# Steering_IOSch.net
KiCad netlist of a schematic drawn in Altium Designer
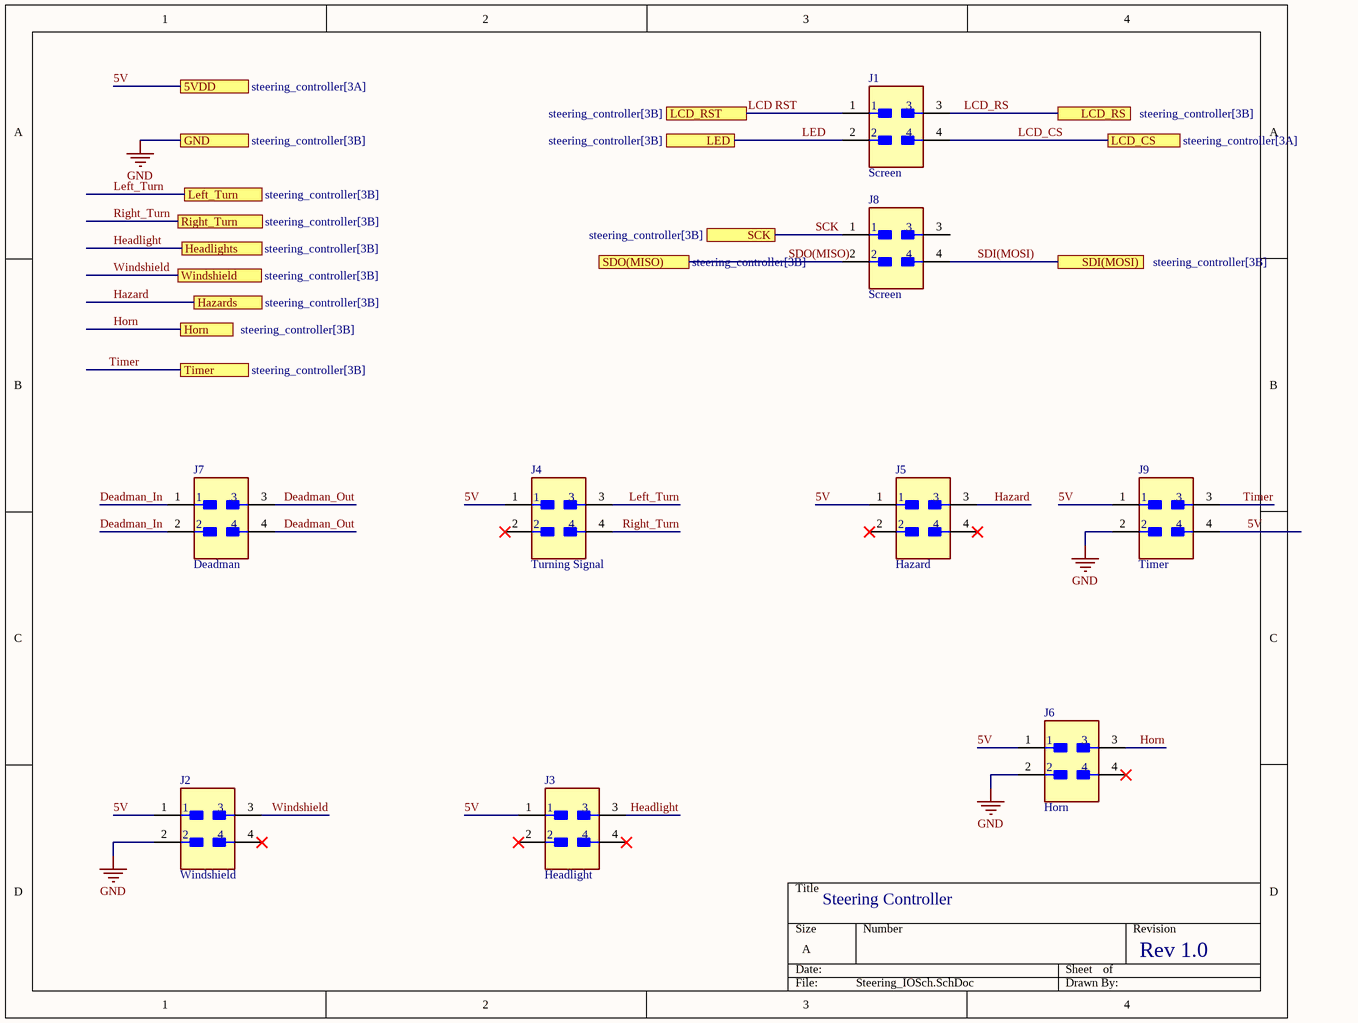
[diagram p0: Steering_IOSch.SchDoc]

(export (version "E")
  (design (tool "Eeschema 10.0.6"))
  (components
    (comp (ref "J1")
      (value "Screen")
      (footprint "asib:FP-0039281043-MFG")
      (description "CONN HEADER VERT 4POS 4.2MM. 0039281043")
      (fields (field (name "MANUFACTURER PART NUMBER") "0039281043") (field (name "MANUFACTURER") "Molex"))
      (libsource (lib "asib") (part "1x4_FEMALE_POWER"))
    )
    (comp (ref "J2")
      (value "Windshield")
      (footprint "asib:FP-0039281043-MFG")
      (description "CONN HEADER VERT 4POS 4.2MM. 0039281043")
      (fields (field (name "MANUFACTURER PART NUMBER") "0039281043") (field (name "MANUFACTURER") "Molex"))
      (libsource (lib "asib") (part "1x4_FEMALE_POWER"))
    )
    (comp (ref "J3")
      (value "Headlight")
      (footprint "asib:FP-0039281043-MFG")
      (description "CONN HEADER VERT 4POS 4.2MM. 0039281043")
      (fields (field (name "MANUFACTURER PART NUMBER") "0039281043") (field (name "MANUFACTURER") "Molex"))
      (libsource (lib "asib") (part "1x4_FEMALE_POWER"))
    )
    (comp (ref "J4")
      (value "Turning Signal")
      (footprint "asib:FP-0039281043-MFG")
      (description "CONN HEADER VERT 4POS 4.2MM. 0039281043")
      (fields (field (name "MANUFACTURER PART NUMBER") "0039281043") (field (name "MANUFACTURER") "Molex"))
      (libsource (lib "asib") (part "1x4_FEMALE_POWER"))
    )
    (comp (ref "J5")
      (value "Hazard")
      (footprint "asib:FP-0039281043-MFG")
      (description "CONN HEADER VERT 4POS 4.2MM. 0039281043")
      (fields (field (name "MANUFACTURER PART NUMBER") "0039281043") (field (name "MANUFACTURER") "Molex"))
      (libsource (lib "asib") (part "1x4_FEMALE_POWER"))
    )
    (comp (ref "J6")
      (value "Horn")
      (footprint "asib:FP-0039281043-MFG")
      (description "CONN HEADER VERT 4POS 4.2MM. 0039281043")
      (fields (field (name "MANUFACTURER PART NUMBER") "0039281043") (field (name "MANUFACTURER") "Molex"))
      (libsource (lib "asib") (part "1x4_FEMALE_POWER"))
    )
    (comp (ref "J7")
      (value "Deadman")
      (footprint "asib:FP-0039281043-MFG")
      (description "CONN HEADER VERT 4POS 4.2MM. 0039281043")
      (fields (field (name "MANUFACTURER PART NUMBER") "0039281043") (field (name "MANUFACTURER") "Molex"))
      (libsource (lib "asib") (part "1x4_FEMALE_POWER"))
    )
    (comp (ref "J8")
      (value "Screen")
      (footprint "asib:FP-0039281043-MFG")
      (description "CONN HEADER VERT 4POS 4.2MM. 0039281043")
      (fields (field (name "MANUFACTURER PART NUMBER") "0039281043") (field (name "MANUFACTURER") "Molex"))
      (libsource (lib "asib") (part "1x4_FEMALE_POWER"))
    )
    (comp (ref "J9")
      (value "Timer")
      (footprint "asib:FP-0039281043-MFG")
      (description "CONN HEADER VERT 4POS 4.2MM. 0039281043")
      (fields (field (name "MANUFACTURER PART NUMBER") "0039281043") (field (name "MANUFACTURER") "Molex"))
      (libsource (lib "asib") (part "1x4_FEMALE_POWER"))
    )
  )
  (nets
    (net (code "1") (name "/5V") (class "Default")
      (node (ref "J2") (pin "1") (pinfunction "1_1") (pintype "passive"))
      (node (ref "J3") (pin "1") (pinfunction "1_1") (pintype "passive"))
      (node (ref "J4") (pin "1") (pinfunction "1_1") (pintype "passive"))
      (node (ref "J5") (pin "1") (pinfunction "1_1") (pintype "passive"))
      (node (ref "J6") (pin "1") (pinfunction "1_1") (pintype "passive"))
      (node (ref "J9") (pin "1") (pinfunction "1_1") (pintype "passive"))
      (node (ref "J9") (pin "4") (pinfunction "4_4") (pintype "passive"))
    )
    (net (code "2") (name "/Deadman_In") (class "Default")
      (node (ref "J7") (pin "1") (pinfunction "1_1") (pintype "passive"))
      (node (ref "J7") (pin "2") (pinfunction "2_2") (pintype "passive"))
    )
    (net (code "3") (name "/Deadman_Out") (class "Default")
      (node (ref "J7") (pin "3") (pinfunction "3_3") (pintype "passive"))
      (node (ref "J7") (pin "4") (pinfunction "4_4") (pintype "passive"))
    )
    (net (code "4") (name "/Hazard") (class "Default")
      (node (ref "J5") (pin "3") (pinfunction "3_3") (pintype "passive"))
    )
    (net (code "5") (name "/Headlight") (class "Default")
      (node (ref "J3") (pin "3") (pinfunction "3_3") (pintype "passive"))
    )
    (net (code "6") (name "/Horn") (class "Default")
      (node (ref "J6") (pin "3") (pinfunction "3_3") (pintype "passive"))
    )
    (net (code "7") (name "/LCD RST") (class "Default")
      (node (ref "J1") (pin "1") (pinfunction "1_1") (pintype "passive"))
    )
    (net (code "8") (name "/LCD_CS") (class "Default")
      (node (ref "J1") (pin "4") (pinfunction "4_4") (pintype "passive"))
    )
    (net (code "9") (name "/LCD_RS") (class "Default")
      (node (ref "J1") (pin "3") (pinfunction "3_3") (pintype "passive"))
    )
    (net (code "10") (name "/LED") (class "Default")
      (node (ref "J1") (pin "2") (pinfunction "2_2") (pintype "passive"))
    )
    (net (code "11") (name "/Left_Turn") (class "Default")
      (node (ref "J4") (pin "3") (pinfunction "3_3") (pintype "passive"))
    )
    (net (code "12") (name "/Right_Turn") (class "Default")
      (node (ref "J4") (pin "4") (pinfunction "4_4") (pintype "passive"))
    )
    (net (code "13") (name "/SCK") (class "Default")
      (node (ref "J8") (pin "1") (pinfunction "1_1") (pintype "passive"))
    )
    (net (code "14") (name "/SDI(MOSI)") (class "Default")
      (node (ref "J8") (pin "4") (pinfunction "4_4") (pintype "passive"))
    )
    (net (code "15") (name "/SDO(MISO)") (class "Default")
      (node (ref "J8") (pin "2") (pinfunction "2_2") (pintype "passive"))
    )
    (net (code "16") (name "/Timer") (class "Default")
      (node (ref "J9") (pin "3") (pinfunction "3_3") (pintype "passive"))
    )
    (net (code "17") (name "/Windshield") (class "Default")
      (node (ref "J2") (pin "3") (pinfunction "3_3") (pintype "passive"))
    )
    (net (code "18") (name "GND") (class "Default")
      (node (ref "J2") (pin "2") (pinfunction "2_2") (pintype "passive"))
      (node (ref "J6") (pin "2") (pinfunction "2_2") (pintype "passive"))
      (node (ref "J9") (pin "2") (pinfunction "2_2") (pintype "passive"))
    )
    (net (code "19") (name "unconnected-(J2-Pad4)") (class "Default")
      (node (ref "J2") (pin "4") (pinfunction "4_4") (pintype "passive+no_connect"))
    )
    (net (code "20") (name "unconnected-(J3-Pad2)") (class "Default")
      (node (ref "J3") (pin "2") (pinfunction "2_2") (pintype "passive+no_connect"))
    )
    (net (code "21") (name "unconnected-(J3-Pad4)") (class "Default")
      (node (ref "J3") (pin "4") (pinfunction "4_4") (pintype "passive+no_connect"))
    )
    (net (code "22") (name "unconnected-(J4-Pad2)") (class "Default")
      (node (ref "J4") (pin "2") (pinfunction "2_2") (pintype "passive+no_connect"))
    )
    (net (code "23") (name "unconnected-(J5-Pad2)") (class "Default")
      (node (ref "J5") (pin "2") (pinfunction "2_2") (pintype "passive+no_connect"))
    )
    (net (code "24") (name "unconnected-(J5-Pad4)") (class "Default")
      (node (ref "J5") (pin "4") (pinfunction "4_4") (pintype "passive+no_connect"))
    )
    (net (code "25") (name "unconnected-(J6-Pad4)") (class "Default")
      (node (ref "J6") (pin "4") (pinfunction "4_4") (pintype "passive+no_connect"))
    )
    (net (code "26") (name "unconnected-(J8-Pad3)") (class "Default")
      (node (ref "J8") (pin "3") (pinfunction "3_3") (pintype "passive"))
    )
  )
)
